# powerboard.net
KiCad netlist of a schematic drawn in EAGLE
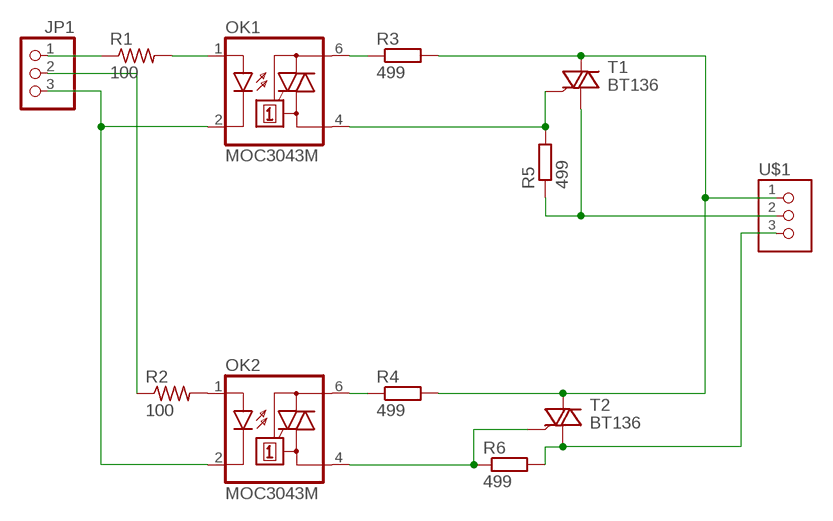
[diagram p0: schematic, sheet 1]

(export (version "E")
  (design (tool "Eeschema 10.0.6"))
  (components
    (comp (ref "JP1")
      (value "PINHD-1X3/90")
      (footprint "eagle-import:1X03_90")
      (libsource (lib "eagle-import") (part "PINHD-1X3/90"))
    )
    (comp (ref "OK1")
      (value "MOC3043M")
      (footprint "eagle-import:DIL06")
      (fields (field (name "MF") "FAIRCHILD SEMICONDUCTOR") (field (name "MPN") "MOC3043-M"))
      (libsource (lib "eagle-import") (part "MOC3043M"))
    )
    (comp (ref "OK2")
      (value "MOC3043M")
      (footprint "eagle-import:DIL06")
      (fields (field (name "MF") "FAIRCHILD SEMICONDUCTOR") (field (name "MPN") "MOC3043-M"))
      (libsource (lib "eagle-import") (part "MOC3043M"))
    )
    (comp (ref "R1")
      (value "100")
      (footprint "eagle-import:R1206FAB")
      (libsource (lib "eagle-import") (part "RES-US1206FAB"))
    )
    (comp (ref "R2")
      (value "100")
      (footprint "eagle-import:R1206FAB")
      (libsource (lib "eagle-import") (part "RES-US1206FAB"))
    )
    (comp (ref "R3")
      (value "499")
      (footprint "eagle-import:0207_12")
      (libsource (lib "eagle-import") (part "R-EU_0207/12"))
    )
    (comp (ref "R4")
      (value "499")
      (footprint "eagle-import:0207_12")
      (libsource (lib "eagle-import") (part "R-EU_0207/12"))
    )
    (comp (ref "R5")
      (value "499")
      (footprint "eagle-import:0207_12")
      (libsource (lib "eagle-import") (part "R-EU_0207/12"))
    )
    (comp (ref "R6")
      (value "499")
      (footprint "eagle-import:0207_12")
      (libsource (lib "eagle-import") (part "R-EU_0207/12"))
    )
    (comp (ref "T1")
      (value "BT136")
      (footprint "eagle-import:TO220AB")
      (libsource (lib "eagle-import") (part "BT136"))
    )
    (comp (ref "T2")
      (value "BT136")
      (footprint "eagle-import:TO220AB")
      (libsource (lib "eagle-import") (part "BT136"))
    )
    (comp (ref "U$1")
      (value "TERM-1X03'-FABLAB'")
      (footprint "eagle-import:ED555DS-3DS")
      (libsource (lib "eagle-import") (part "TERM-1X03'-FABLAB'"))
    )
  )
  (nets
    (net (code "1") (name "Net-(JP1-Pad1)") (class "Default")
      (node (ref "JP1") (pin "1") (pinfunction "1_1") (pintype "passive"))
      (node (ref "R1") (pin "1") (pinfunction "1_1") (pintype "passive"))
    )
    (net (code "2") (name "Net-(JP1-Pad2)") (class "Default")
      (node (ref "JP1") (pin "2") (pinfunction "2_2") (pintype "passive"))
      (node (ref "R2") (pin "1") (pinfunction "1_1") (pintype "passive"))
    )
    (net (code "3") (name "Net-(OK1-A)") (class "Default")
      (node (ref "OK1") (pin "1") (pinfunction "A_1") (pintype "passive"))
      (node (ref "R1") (pin "2") (pinfunction "2_2") (pintype "passive"))
    )
    (net (code "4") (name "Net-(OK1-A1)") (class "Default")
      (node (ref "OK1") (pin "4") (pinfunction "A1_4") (pintype "passive"))
      (node (ref "R5") (pin "2") (pinfunction "2_2") (pintype "passive"))
      (node (ref "T1") (pin "3") (pinfunction "G_3") (pintype "passive"))
    )
    (net (code "5") (name "Net-(OK1-A2)") (class "Default")
      (node (ref "OK1") (pin "6") (pinfunction "A2_6") (pintype "passive"))
      (node (ref "R3") (pin "1") (pinfunction "1_1") (pintype "passive"))
    )
    (net (code "6") (name "Net-(OK1-C)") (class "Default")
      (node (ref "JP1") (pin "3") (pinfunction "3_3") (pintype "passive"))
      (node (ref "OK1") (pin "2") (pinfunction "C_2") (pintype "passive"))
      (node (ref "OK2") (pin "2") (pinfunction "C_2") (pintype "passive"))
    )
    (net (code "7") (name "Net-(OK2-A)") (class "Default")
      (node (ref "OK2") (pin "1") (pinfunction "A_1") (pintype "passive"))
      (node (ref "R2") (pin "2") (pinfunction "2_2") (pintype "passive"))
    )
    (net (code "8") (name "Net-(OK2-A1)") (class "Default")
      (node (ref "OK2") (pin "4") (pinfunction "A1_4") (pintype "passive"))
      (node (ref "R6") (pin "1") (pinfunction "1_1") (pintype "passive"))
      (node (ref "T2") (pin "3") (pinfunction "G_3") (pintype "passive"))
    )
    (net (code "9") (name "Net-(OK2-A2)") (class "Default")
      (node (ref "OK2") (pin "6") (pinfunction "A2_6") (pintype "passive"))
      (node (ref "R4") (pin "1") (pinfunction "1_1") (pintype "passive"))
    )
    (net (code "10") (name "Net-(T1-A1)") (class "Default")
      (node (ref "R5") (pin "1") (pinfunction "1_1") (pintype "passive"))
      (node (ref "T1") (pin "1") (pinfunction "A1_1") (pintype "passive"))
      (node (ref "U$1") (pin "2") (pinfunction "2_2") (pintype "passive"))
    )
    (net (code "11") (name "Net-(T1-A2)") (class "Default")
      (node (ref "R3") (pin "2") (pinfunction "2_2") (pintype "passive"))
      (node (ref "R4") (pin "2") (pinfunction "2_2") (pintype "passive"))
      (node (ref "T1") (pin "2") (pinfunction "A2_2") (pintype "passive"))
      (node (ref "T2") (pin "2") (pinfunction "A2_2") (pintype "passive"))
      (node (ref "U$1") (pin "1") (pinfunction "1_1") (pintype "passive"))
    )
    (net (code "12") (name "Net-(T2-A1)") (class "Default")
      (node (ref "R6") (pin "2") (pinfunction "2_2") (pintype "passive"))
      (node (ref "T2") (pin "1") (pinfunction "A1_1") (pintype "passive"))
      (node (ref "U$1") (pin "3") (pinfunction "3_3") (pintype "passive"))
    )
  )
)
